# FireLamp_WeMosD1Mini_Shield_1_0.net
KiCad netlist of a schematic drawn in EAGLE
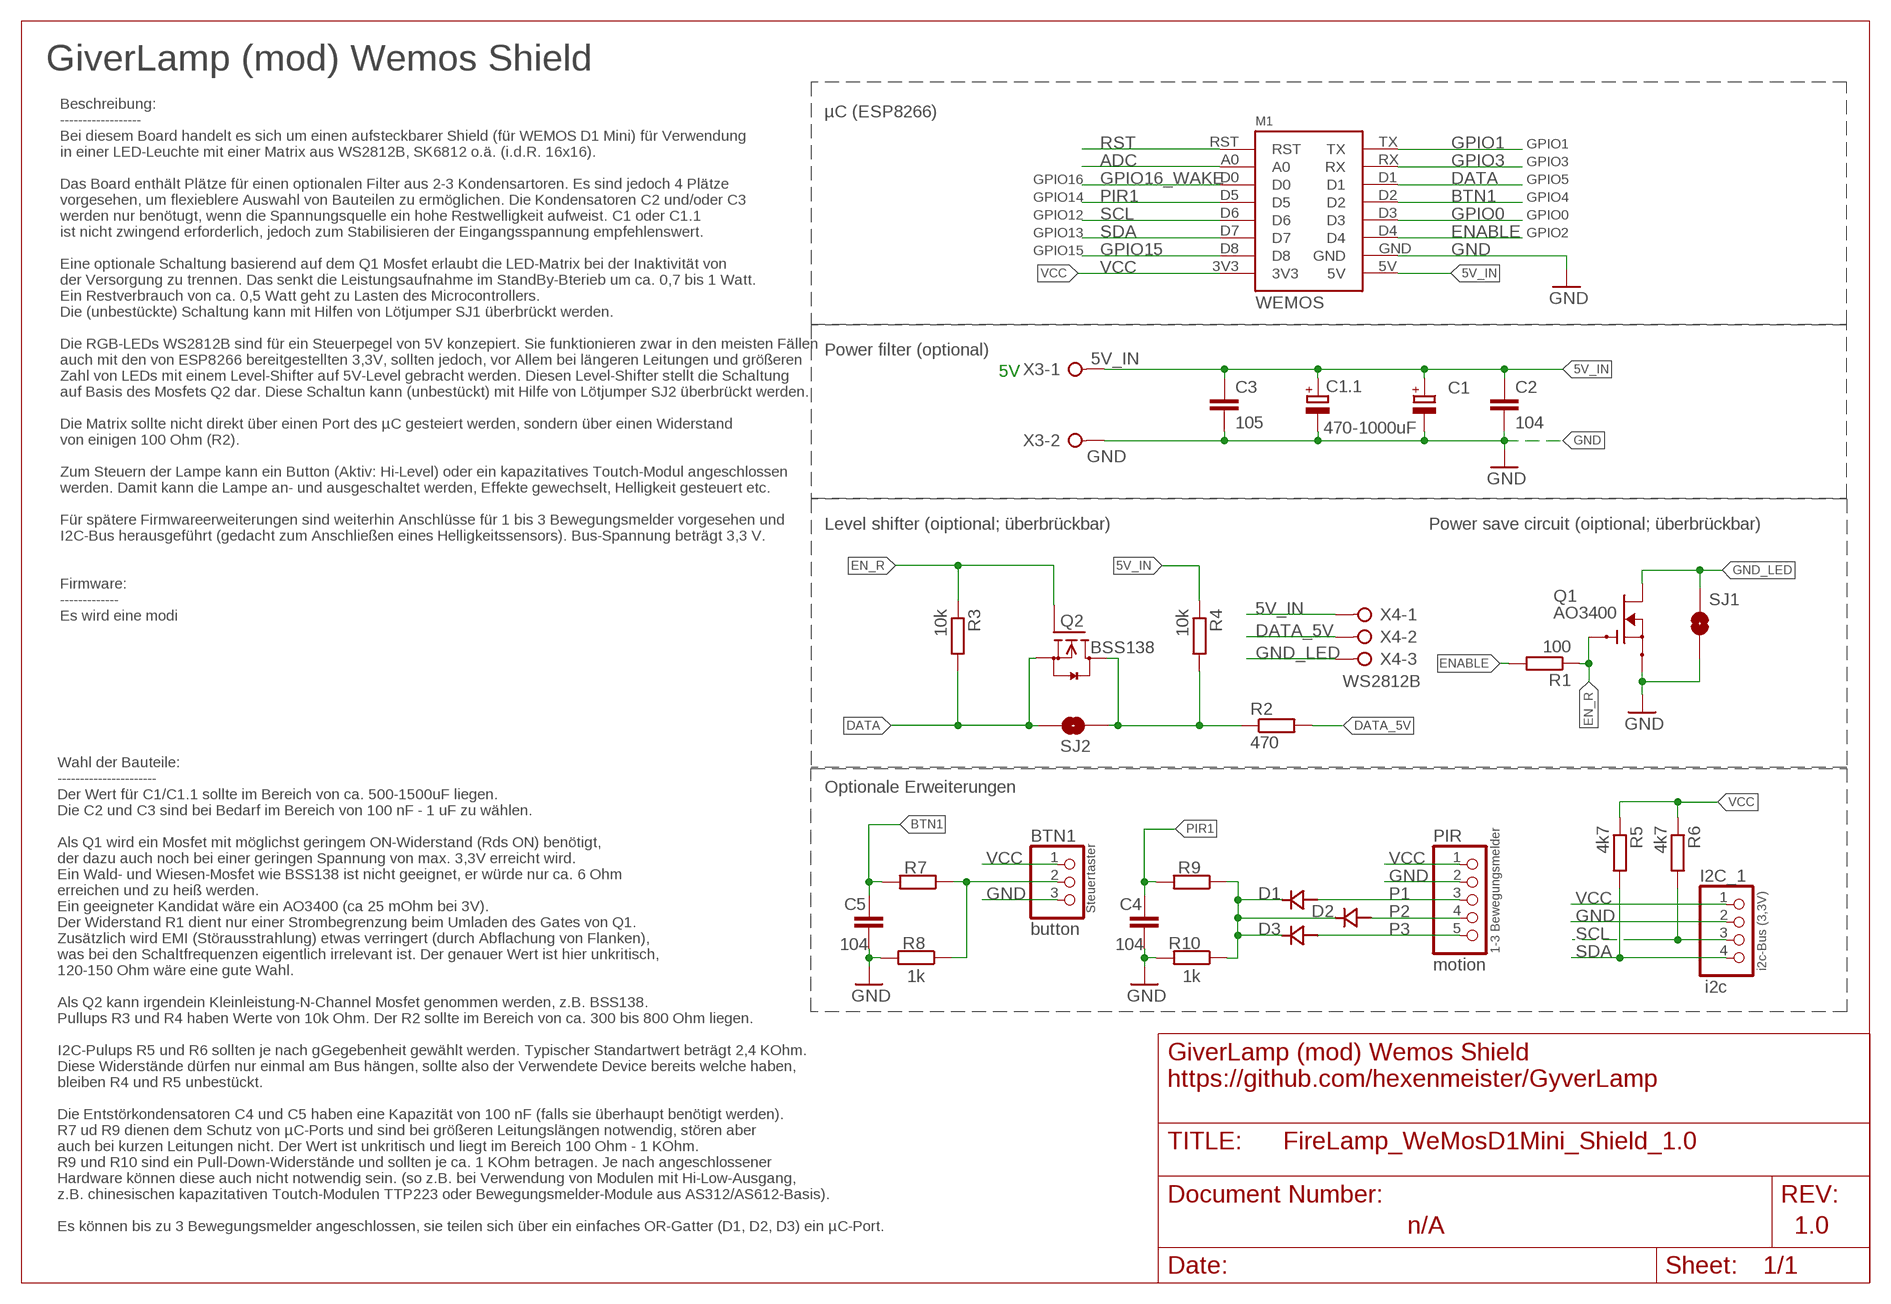
[diagram p0: schematic, sheet 1]

(export (version "E")
  (design (tool "Eeschema 10.0.6"))
  (components
    (comp (ref "BTN1")
      (value "button")
      (footprint "eagle-import:1X03")
      (libsource (lib "eagle-import") (part "PINHD-1X3_S"))
    )
    (comp (ref "C1")
      (value "470-1000uF")
      (footprint "eagle-import:E2,5-6E")
      (libsource (lib "eagle-import") (part "CPOL-EUE2,5-6E"))
    )
    (comp (ref "C1.1")
      (value "CPOL-EU140CLH-1010")
      (footprint "eagle-import:140CLH-1010")
      (libsource (lib "eagle-import") (part "CPOL-EU140CLH-1010"))
    )
    (comp (ref "C2")
      (value "104")
      (footprint "eagle-import:C0805")
      (libsource (lib "eagle-import") (part "C-EUC0805"))
    )
    (comp (ref "C3")
      (value "105")
      (footprint "eagle-import:MY1210")
      (libsource (lib "eagle-import") (part "C"))
    )
    (comp (ref "C4")
      (value "104")
      (footprint "eagle-import:C0805")
      (libsource (lib "eagle-import") (part "C-EUC0805"))
    )
    (comp (ref "C5")
      (value "104")
      (footprint "eagle-import:C0805")
      (libsource (lib "eagle-import") (part "C-EUC0805"))
    )
    (comp (ref "D1")
      (value "SS14")
      (footprint "eagle-import:DO214")
      (libsource (lib "eagle-import") (part "SS14"))
    )
    (comp (ref "D2")
      (value "SS14")
      (footprint "eagle-import:DO214")
      (libsource (lib "eagle-import") (part "SS14"))
    )
    (comp (ref "D3")
      (value "SS14")
      (footprint "eagle-import:DO214")
      (libsource (lib "eagle-import") (part "SS14"))
    )
    (comp (ref "I2C_1")
      (value "i2c")
      (footprint "eagle-import:1X04")
      (libsource (lib "eagle-import") (part "PINHD-1X4_S"))
    )
    (comp (ref "M1")
      (value "WEMOS")
      (footprint "eagle-import:WEMOS")
      (libsource (lib "eagle-import") (part "WEMOS"))
    )
    (comp (ref "PIR")
      (value "motion")
      (footprint "eagle-import:1X05")
      (libsource (lib "eagle-import") (part "PINHD-1X5_S"))
    )
    (comp (ref "Q1")
      (value "AO3400")
      (footprint "eagle-import:SOT23")
      (fields (field (name "MF") "Alpha &"))
      (libsource (lib "eagle-import") (part "AO3400"))
    )
    (comp (ref "Q2")
      (value "BSS138")
      (footprint "eagle-import:SOT23")
      (libsource (lib "eagle-import") (part "BSS138"))
    )
    (comp (ref "R1")
      (value "100")
      (footprint "eagle-import:R0805")
      (libsource (lib "eagle-import") (part "R-EU_R0805"))
    )
    (comp (ref "R2")
      (value "470")
      (footprint "eagle-import:R0805")
      (libsource (lib "eagle-import") (part "R-EU_R0805"))
    )
    (comp (ref "R3")
      (value "10k")
      (footprint "eagle-import:R0805")
      (libsource (lib "eagle-import") (part "R-EU_R0805"))
    )
    (comp (ref "R4")
      (value "10k")
      (footprint "eagle-import:R0805")
      (libsource (lib "eagle-import") (part "R-EU_R0805"))
    )
    (comp (ref "R5")
      (value "4k7")
      (footprint "eagle-import:R0805")
      (libsource (lib "eagle-import") (part "R-EU_R0805"))
    )
    (comp (ref "R6")
      (value "4k7")
      (footprint "eagle-import:R0805")
      (libsource (lib "eagle-import") (part "R-EU_R0805"))
    )
    (comp (ref "R7")
      (value "100")
      (footprint "eagle-import:R0805_SMALL_GAP")
      (libsource (lib "eagle-import") (part "R0805_SMALL_GAP"))
    )
    (comp (ref "R8")
      (value "1k")
      (footprint "eagle-import:R0805")
      (libsource (lib "eagle-import") (part "R-EU_R0805"))
    )
    (comp (ref "R9")
      (value "100")
      (footprint "eagle-import:R0805_SMALL_GAP")
      (libsource (lib "eagle-import") (part "R0805_SMALL_GAP"))
    )
    (comp (ref "R10")
      (value "1k")
      (footprint "eagle-import:R0805")
      (libsource (lib "eagle-import") (part "R-EU_R0805"))
    )
    (comp (ref "SJ1")
      (value "pwr sv")
      (footprint "eagle-import:PAD-JUMPER-2-NO_YES_SILK")
      (libsource (lib "eagle-import") (part "JUMPER-PAD-2-NOYES_SILK"))
    )
    (comp (ref "SJ2")
      (value "lvl sh")
      (footprint "eagle-import:PAD-JUMPER-2-NO_YES_SILK")
      (libsource (lib "eagle-import") (part "JUMPER-PAD-2-NOYES_SILK"))
    )
    (comp (ref "X3")
      (value "W237-02P")
      (footprint "eagle-import:W237-132")
      (libsource (lib "eagle-import") (part "W237-02P"))
    )
    (comp (ref "X4")
      (value "W237-03P")
      (footprint "eagle-import:W237-133")
      (libsource (lib "eagle-import") (part "W237-03P"))
    )
  )
  (nets
    (net (code "1") (name "/ADC") (class "Default")
      (node (ref "M1") (pin "A0") (pinfunction "A0_A0") (pintype "bidirectional"))
    )
    (net (code "2") (name "/GPIO0") (class "Default")
      (node (ref "M1") (pin "D3") (pinfunction "D3_D3") (pintype "bidirectional"))
    )
    (net (code "3") (name "/GPIO1") (class "Default")
      (node (ref "M1") (pin "TX") (pinfunction "TX_TX") (pintype "bidirectional"))
    )
    (net (code "4") (name "/GPIO3") (class "Default")
      (node (ref "M1") (pin "RX") (pinfunction "RX_RX") (pintype "bidirectional"))
    )
    (net (code "5") (name "/GPIO15") (class "Default")
      (node (ref "M1") (pin "D8") (pinfunction "D8_D8") (pintype "bidirectional"))
    )
    (net (code "6") (name "/GPIO16_WAKE") (class "Default")
      (node (ref "M1") (pin "D0") (pinfunction "D0_D0") (pintype "bidirectional"))
    )
    (net (code "7") (name "/P1") (class "Default")
      (node (ref "D1") (pin "ANODE") (pinfunction "ANODE_ANODE") (pintype "bidirectional"))
      (node (ref "PIR") (pin "3") (pinfunction "3_3") (pintype "passive"))
    )
    (net (code "8") (name "/P2") (class "Default")
      (node (ref "D2") (pin "ANODE") (pinfunction "ANODE_ANODE") (pintype "bidirectional"))
      (node (ref "PIR") (pin "4") (pinfunction "4_4") (pintype "passive"))
    )
    (net (code "9") (name "/P3") (class "Default")
      (node (ref "D3") (pin "ANODE") (pinfunction "ANODE_ANODE") (pintype "bidirectional"))
      (node (ref "PIR") (pin "5") (pinfunction "5_5") (pintype "passive"))
    )
    (net (code "10") (name "/RST") (class "Default")
      (node (ref "M1") (pin "RST") (pinfunction "RST_RST") (pintype "bidirectional"))
    )
    (net (code "11") (name "/SCL") (class "Default")
      (node (ref "I2C_1") (pin "3") (pinfunction "3_3") (pintype "passive"))
      (node (ref "M1") (pin "D6") (pinfunction "D6_D6") (pintype "bidirectional"))
      (node (ref "R6") (pin "2") (pinfunction "2_2") (pintype "passive"))
    )
    (net (code "12") (name "/SDA") (class "Default")
      (node (ref "I2C_1") (pin "4") (pinfunction "4_4") (pintype "passive"))
      (node (ref "M1") (pin "D7") (pinfunction "D7_D7") (pintype "bidirectional"))
      (node (ref "R5") (pin "2") (pinfunction "2_2") (pintype "passive"))
    )
    (net (code "13") (name "5V_IN") (class "Default")
      (node (ref "C1") (pin "+") (pinfunction "+_+") (pintype "passive"))
      (node (ref "C1.1") (pin "+") (pinfunction "+_+") (pintype "passive"))
      (node (ref "C2") (pin "1") (pinfunction "1_1") (pintype "passive"))
      (node (ref "C3") (pin "1") (pinfunction "1_1") (pintype "passive"))
      (node (ref "M1") (pin "5V") (pinfunction "5V_5V") (pintype "bidirectional"))
      (node (ref "R4") (pin "1") (pinfunction "1_1") (pintype "passive"))
      (node (ref "X3") (pin "1") (pinfunction "KL_1") (pintype "passive"))
      (node (ref "X4") (pin "1") (pinfunction "KL_1") (pintype "passive"))
    )
    (net (code "14") (name "BTN1") (class "Default")
      (node (ref "C5") (pin "1") (pinfunction "1_1") (pintype "passive"))
      (node (ref "M1") (pin "D2") (pinfunction "D2_D2") (pintype "bidirectional"))
      (node (ref "R7") (pin "2") (pinfunction "2_2") (pintype "passive"))
    )
    (net (code "15") (name "DATA") (class "Default")
      (node (ref "M1") (pin "D1") (pinfunction "D1_D1") (pintype "bidirectional"))
      (node (ref "Q2") (pin "2") (pinfunction "S_2") (pintype "passive"))
      (node (ref "R3") (pin "2") (pinfunction "2_2") (pintype "passive"))
      (node (ref "SJ2") (pin "1") (pinfunction "1_1") (pintype "passive"))
    )
    (net (code "16") (name "DATA_5V") (class "Default")
      (node (ref "R2") (pin "2") (pinfunction "2_2") (pintype "passive"))
      (node (ref "X4") (pin "2") (pinfunction "KL_2") (pintype "passive"))
    )
    (net (code "17") (name "ENABLE") (class "Default")
      (node (ref "M1") (pin "D4") (pinfunction "D4_D4") (pintype "bidirectional"))
      (node (ref "R1") (pin "2") (pinfunction "2_2") (pintype "passive"))
    )
    (net (code "18") (name "EN_R") (class "Default")
      (node (ref "Q1") (pin "1") (pinfunction "G_1") (pintype "passive"))
      (node (ref "Q2") (pin "1") (pinfunction "G_1") (pintype "passive"))
      (node (ref "R1") (pin "1") (pinfunction "1_1") (pintype "passive"))
      (node (ref "R3") (pin "1") (pinfunction "1_1") (pintype "passive"))
    )
    (net (code "19") (name "GND") (class "Default")
      (node (ref "BTN1") (pin "3") (pinfunction "3_3") (pintype "passive"))
      (node (ref "C1") (pin "-") (pinfunction "-_-") (pintype "passive"))
      (node (ref "C1.1") (pin "-") (pinfunction "-_-") (pintype "passive"))
      (node (ref "C2") (pin "2") (pinfunction "2_2") (pintype "passive"))
      (node (ref "C3") (pin "2") (pinfunction "2_2") (pintype "passive"))
      (node (ref "C4") (pin "2") (pinfunction "2_2") (pintype "passive"))
      (node (ref "C5") (pin "2") (pinfunction "2_2") (pintype "passive"))
      (node (ref "I2C_1") (pin "2") (pinfunction "2_2") (pintype "passive"))
      (node (ref "M1") (pin "GND") (pinfunction "GND_GND") (pintype "bidirectional"))
      (node (ref "PIR") (pin "2") (pinfunction "2_2") (pintype "passive"))
      (node (ref "Q1") (pin "2") (pinfunction "S_2") (pintype "passive"))
      (node (ref "R10") (pin "2") (pinfunction "2_2") (pintype "passive"))
      (node (ref "R8") (pin "2") (pinfunction "2_2") (pintype "passive"))
      (node (ref "SJ1") (pin "2") (pinfunction "2_2") (pintype "passive"))
      (node (ref "X3") (pin "2") (pinfunction "KL_2") (pintype "passive"))
    )
    (net (code "20") (name "GND_LED") (class "Default")
      (node (ref "Q1") (pin "3") (pinfunction "D_3") (pintype "passive"))
      (node (ref "SJ1") (pin "1") (pinfunction "1_1") (pintype "passive"))
      (node (ref "X4") (pin "3") (pinfunction "KL_3") (pintype "passive"))
    )
    (net (code "21") (name "Net-(BTN1-Pad2)") (class "Default")
      (node (ref "BTN1") (pin "2") (pinfunction "2_2") (pintype "passive"))
      (node (ref "R7") (pin "1") (pinfunction "1_1") (pintype "passive"))
      (node (ref "R8") (pin "1") (pinfunction "1_1") (pintype "passive"))
    )
    (net (code "22") (name "Net-(D1-PadCATHODE)") (class "Default")
      (node (ref "D1") (pin "CATHODE") (pinfunction "CATHODE_CATHODE") (pintype "bidirectional"))
      (node (ref "D2") (pin "CATHODE") (pinfunction "CATHODE_CATHODE") (pintype "bidirectional"))
      (node (ref "D3") (pin "CATHODE") (pinfunction "CATHODE_CATHODE") (pintype "bidirectional"))
      (node (ref "R10") (pin "1") (pinfunction "1_1") (pintype "passive"))
      (node (ref "R9") (pin "1") (pinfunction "1_1") (pintype "passive"))
    )
    (net (code "23") (name "Net-(Q2-D)") (class "Default")
      (node (ref "Q2") (pin "3") (pinfunction "D_3") (pintype "passive"))
      (node (ref "R2") (pin "1") (pinfunction "1_1") (pintype "passive"))
      (node (ref "R4") (pin "2") (pinfunction "2_2") (pintype "passive"))
      (node (ref "SJ2") (pin "2") (pinfunction "2_2") (pintype "passive"))
    )
    (net (code "24") (name "PIR1") (class "Default")
      (node (ref "C4") (pin "1") (pinfunction "1_1") (pintype "passive"))
      (node (ref "M1") (pin "D5") (pinfunction "D5_D5") (pintype "bidirectional"))
      (node (ref "R9") (pin "2") (pinfunction "2_2") (pintype "passive"))
    )
    (net (code "25") (name "VCC") (class "Default")
      (node (ref "BTN1") (pin "1") (pinfunction "1_1") (pintype "passive"))
      (node (ref "I2C_1") (pin "1") (pinfunction "1_1") (pintype "passive"))
      (node (ref "M1") (pin "3V3") (pinfunction "3V3_3V3") (pintype "bidirectional"))
      (node (ref "PIR") (pin "1") (pinfunction "1_1") (pintype "passive"))
      (node (ref "R5") (pin "1") (pinfunction "1_1") (pintype "passive"))
      (node (ref "R6") (pin "1") (pinfunction "1_1") (pintype "passive"))
    )
  )
)
